# 02A-005.net
KiCad netlist of a schematic drawn in EAGLE
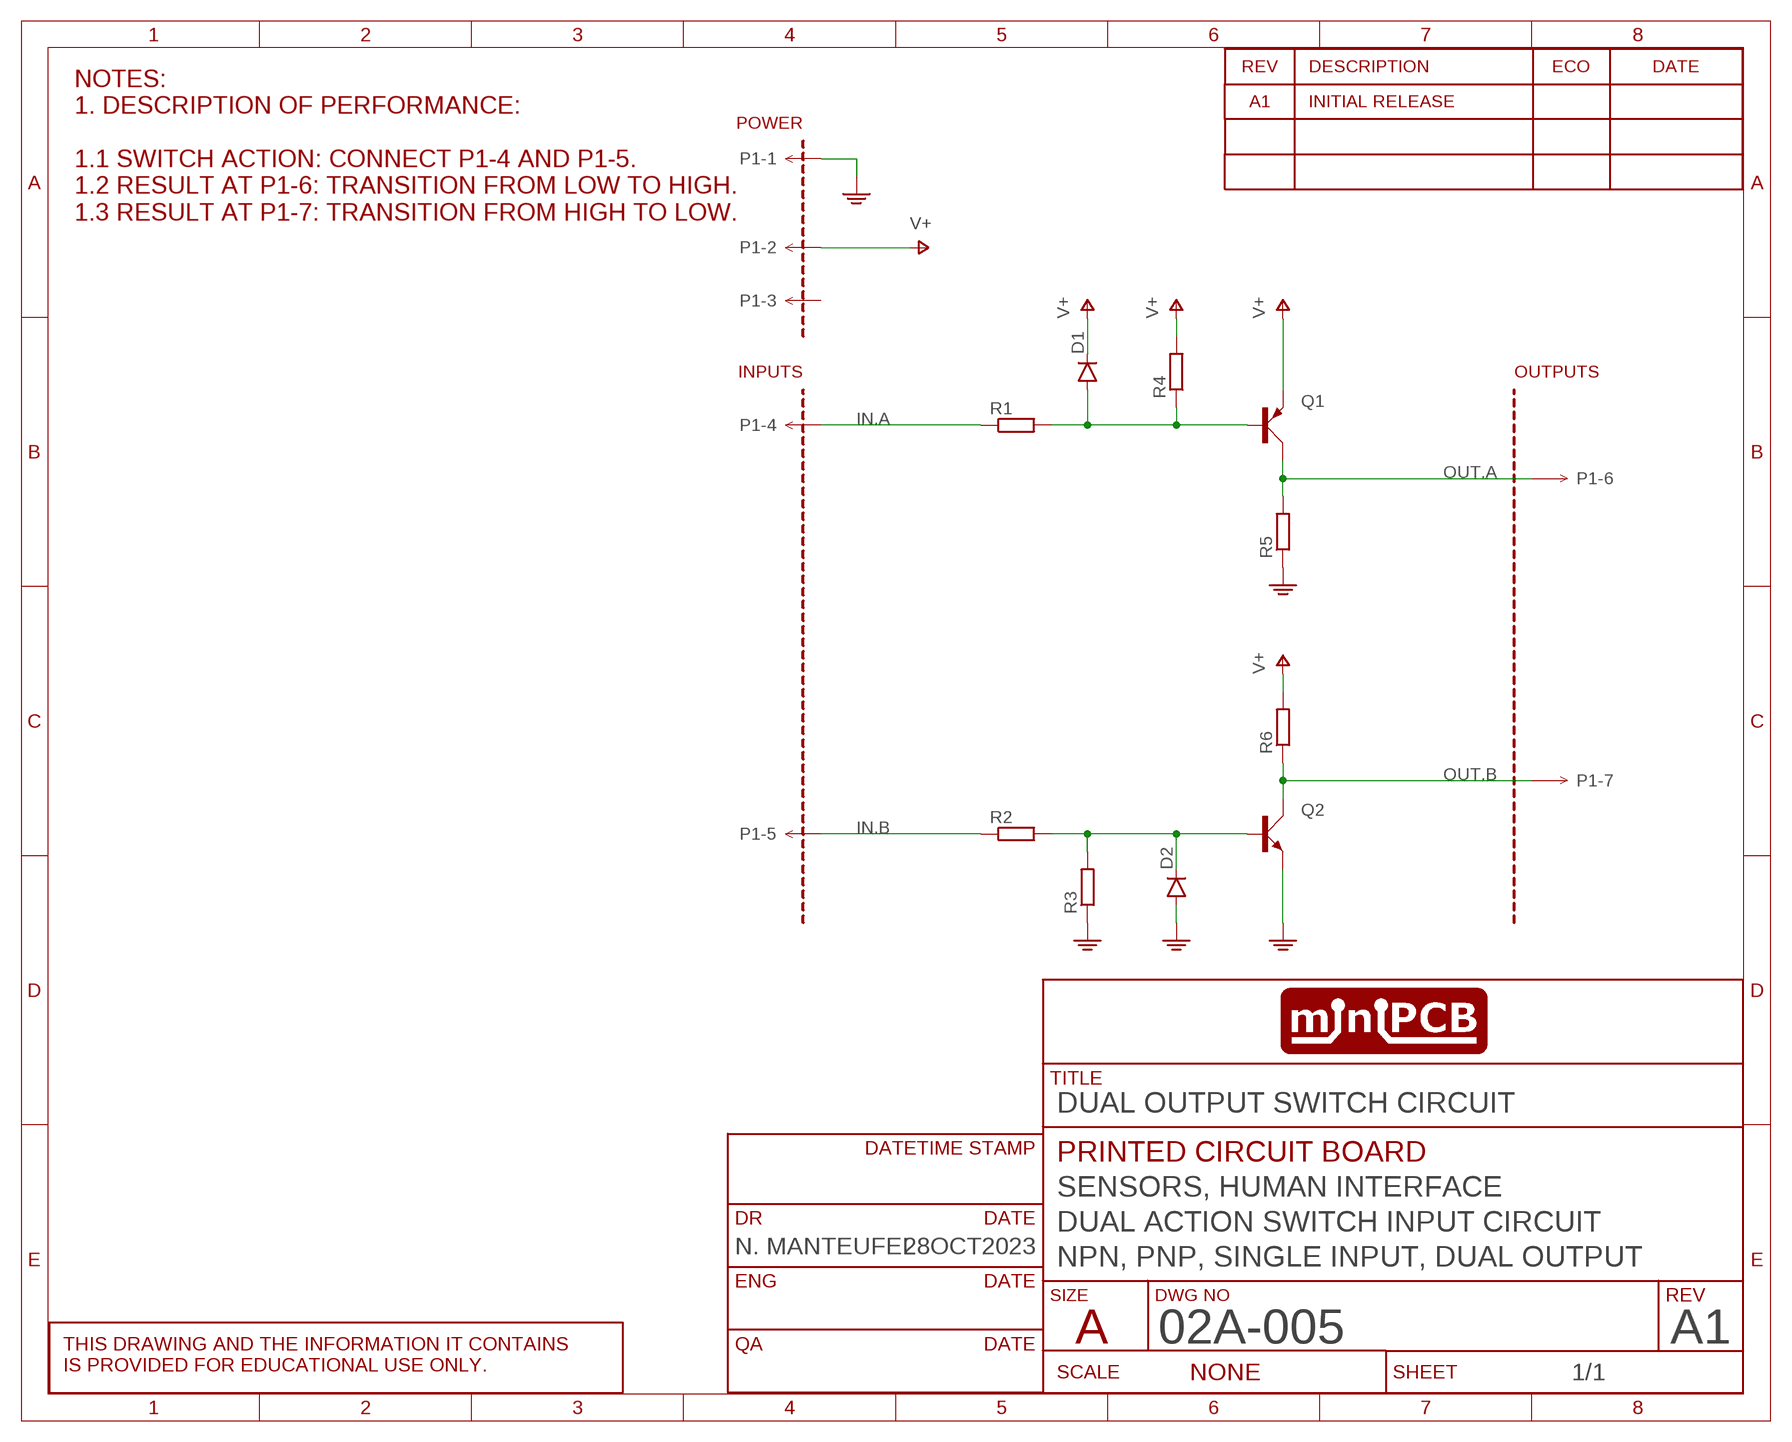
[diagram p0: schematic, sheet 1]

(export (version "E")
  (design (tool "Eeschema 10.0.6"))
  (components
    (comp (ref "D1")
      (value "DIODESMD")
      (footprint "eagle-import:DO214AC")
      (libsource (lib "eagle-import") (part "DIODESMD"))
    )
    (comp (ref "D2")
      (value "DIODESMD")
      (footprint "eagle-import:DO214AC")
      (libsource (lib "eagle-import") (part "DIODESMD"))
    )
    (comp (ref "P1")
      (value "MINIPCB_7P")
      (footprint "eagle-import:PINS_1X7")
      (libsource (lib "eagle-import") (part "MINIPCB_7P"))
    )
    (comp (ref "PCB1")
      (value "MINIPCB_0P00A-20X25")
      (footprint "eagle-import:MINIPCB_00A_20X25")
      (fields (field (name "PART_NUMBER") "02A-005") (field (name "REVISION") "A1-01"))
      (libsource (lib "eagle-import") (part "MINIPCB_0P00A-20X25"))
    )
    (comp (ref "Q1")
      (value "BJT_PNPBEC")
      (footprint "eagle-import:SOT23")
      (libsource (lib "eagle-import") (part "BJT_PNPBEC"))
    )
    (comp (ref "Q2")
      (value "BJT_NPNBEC")
      (footprint "eagle-import:SOT23")
      (libsource (lib "eagle-import") (part "BJT_NPNBEC"))
    )
    (comp (ref "R1")
      (value "RESISTORSMD")
      (footprint "eagle-import:R0805")
      (libsource (lib "eagle-import") (part "RESISTORSMD"))
    )
    (comp (ref "R2")
      (value "RESISTORSMD")
      (footprint "eagle-import:R0805")
      (libsource (lib "eagle-import") (part "RESISTORSMD"))
    )
    (comp (ref "R3")
      (value "RESISTORSMD")
      (footprint "eagle-import:R0805")
      (libsource (lib "eagle-import") (part "RESISTORSMD"))
    )
    (comp (ref "R4")
      (value "RESISTORSMD")
      (footprint "eagle-import:R0805")
      (libsource (lib "eagle-import") (part "RESISTORSMD"))
    )
    (comp (ref "R5")
      (value "RESISTORSMD")
      (footprint "eagle-import:R0805")
      (libsource (lib "eagle-import") (part "RESISTORSMD"))
    )
    (comp (ref "R6")
      (value "RESISTORSMD")
      (footprint "eagle-import:R0805")
      (libsource (lib "eagle-import") (part "RESISTORSMD"))
    )
  )
  (nets
    (net (code "1") (name "/IN.A") (class "Default")
      (node (ref "P1") (pin "4") (pinfunction "1_4") (pintype "bidirectional"))
      (node (ref "R1") (pin "1") (pinfunction "1_1") (pintype "passive"))
    )
    (net (code "2") (name "/IN.B") (class "Default")
      (node (ref "P1") (pin "5") (pinfunction "1_5") (pintype "bidirectional"))
      (node (ref "R2") (pin "1") (pinfunction "1_1") (pintype "passive"))
    )
    (net (code "3") (name "/OUT.A") (class "Default")
      (node (ref "P1") (pin "6") (pinfunction "1_6") (pintype "bidirectional"))
      (node (ref "Q1") (pin "3") (pinfunction "C_3") (pintype "passive"))
      (node (ref "R5") (pin "2") (pinfunction "2_2") (pintype "passive"))
    )
    (net (code "4") (name "/OUT.B") (class "Default")
      (node (ref "P1") (pin "7") (pinfunction "1_7") (pintype "bidirectional"))
      (node (ref "Q2") (pin "3") (pinfunction "C_3") (pintype "passive"))
      (node (ref "R6") (pin "1") (pinfunction "1_1") (pintype "passive"))
    )
    (net (code "5") (name "GND") (class "Default")
      (node (ref "D2") (pin "A") (pinfunction "A_A") (pintype "passive"))
      (node (ref "P1") (pin "1") (pinfunction "1_1") (pintype "bidirectional"))
      (node (ref "Q2") (pin "2") (pinfunction "E_2") (pintype "passive"))
      (node (ref "R3") (pin "1") (pinfunction "1_1") (pintype "passive"))
      (node (ref "R5") (pin "1") (pinfunction "1_1") (pintype "passive"))
    )
    (net (code "6") (name "Net-(Q1-B)") (class "Default")
      (node (ref "D1") (pin "A") (pinfunction "A_A") (pintype "passive"))
      (node (ref "Q1") (pin "1") (pinfunction "B_1") (pintype "passive"))
      (node (ref "R1") (pin "2") (pinfunction "2_2") (pintype "passive"))
      (node (ref "R4") (pin "1") (pinfunction "1_1") (pintype "passive"))
    )
    (net (code "7") (name "Net-(Q2-B)") (class "Default")
      (node (ref "D2") (pin "C") (pinfunction "C_C") (pintype "passive"))
      (node (ref "Q2") (pin "1") (pinfunction "B_1") (pintype "passive"))
      (node (ref "R2") (pin "2") (pinfunction "2_2") (pintype "passive"))
      (node (ref "R3") (pin "2") (pinfunction "2_2") (pintype "passive"))
    )
    (net (code "8") (name "V+") (class "Default")
      (node (ref "D1") (pin "C") (pinfunction "C_C") (pintype "passive"))
      (node (ref "P1") (pin "2") (pinfunction "1_2") (pintype "bidirectional"))
      (node (ref "Q1") (pin "2") (pinfunction "E_2") (pintype "passive"))
      (node (ref "R4") (pin "2") (pinfunction "2_2") (pintype "passive"))
      (node (ref "R6") (pin "2") (pinfunction "2_2") (pintype "passive"))
    )
    (net (code "9") (name "unconnected-(P1C-1-Pad3)") (class "Default")
      (node (ref "P1") (pin "3") (pinfunction "1_3") (pintype "bidirectional"))
    )
  )
)
